# schematic.net
KiCad netlist of a schematic drawn in EAGLE
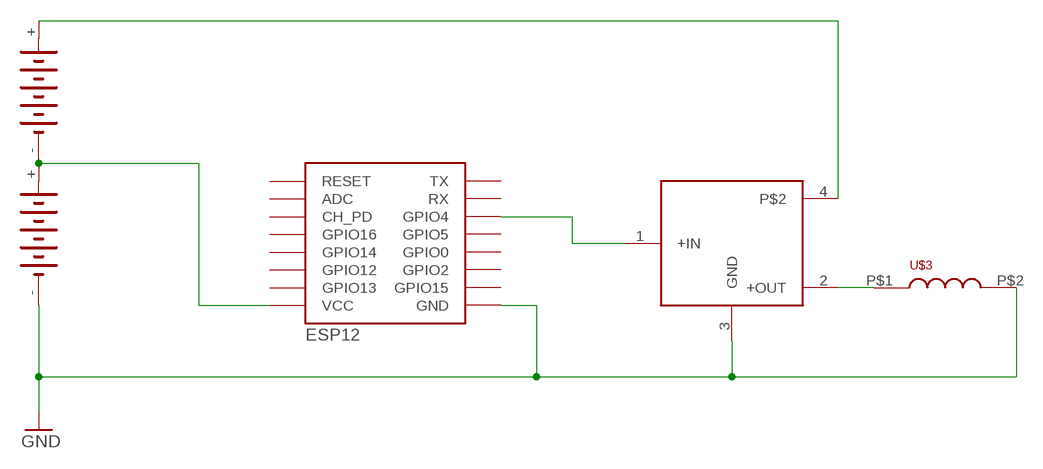
[diagram p0: schematic, sheet 1]

(export (version "E")
  (design (tool "Eeschema 10.0.6"))
  (components
    (comp (ref "G1")
      (value "NC1M")
      (footprint "eagle-import:NC1M")
      (libsource (lib "eagle-import") (part "NC1M"))
    )
    (comp (ref "G2")
      (value "NC1M")
      (footprint "eagle-import:NC1M")
      (libsource (lib "eagle-import") (part "NC1M"))
    )
    (comp (ref "U$1")
      (value "ESP12")
      (footprint "eagle-import:ESP12")
      (libsource (lib "eagle-import") (part "ESP12"))
    )
    (comp (ref "U$2")
      (value "H-BRIDGE")
      (footprint "eagle-import:H-BRIDGE")
      (libsource (lib "eagle-import") (part "H-BRIDGE"))
    )
    (comp (ref "U$3")
      (value "INDUCTOR")
      (footprint "eagle-import:SCD0403T-220M-N")
      (libsource (lib "eagle-import") (part "INDUCTOR"))
    )
  )
  (nets
    (net (code "1") (name "GND") (class "Default")
      (node (ref "G1") (pin "-") (pinfunction "-_-") (pintype "passive"))
      (node (ref "U$1") (pin "GND") (pinfunction "GND_GND") (pintype "bidirectional"))
      (node (ref "U$2") (pin "3") (pinfunction "GND_3") (pintype "bidirectional"))
      (node (ref "U$3") (pin "P$2") (pinfunction "2_P$2") (pintype "bidirectional"))
    )
    (net (code "2") (name "Net-(G1-Pad+)") (class "Default")
      (node (ref "G1") (pin "+") (pinfunction "+_+") (pintype "passive"))
      (node (ref "G2") (pin "-") (pinfunction "-_-") (pintype "passive"))
      (node (ref "U$1") (pin "VCC") (pinfunction "VCC_VCC") (pintype "bidirectional"))
    )
    (net (code "3") (name "Net-(U$2-+IN)") (class "Default")
      (node (ref "U$1") (pin "GPIO4") (pinfunction "GPIO4_GPIO4") (pintype "bidirectional"))
      (node (ref "U$2") (pin "1") (pinfunction "+IN_1") (pintype "bidirectional"))
    )
    (net (code "4") (name "Net-(U$2-+OUT)") (class "Default")
      (node (ref "U$2") (pin "2") (pinfunction "+OUT_2") (pintype "bidirectional"))
      (node (ref "U$3") (pin "P$1") (pinfunction "1_P$1") (pintype "bidirectional"))
    )
    (net (code "5") (name "Net-(U$2-P$2)") (class "Default")
      (node (ref "G2") (pin "+") (pinfunction "+_+") (pintype "passive"))
      (node (ref "U$2") (pin "4") (pinfunction "P$2_4") (pintype "bidirectional"))
    )
    (net (code "6") (name "unconnected-(G1-+-Pad+@1)") (class "Default")
      (node (ref "G1") (pin "+@1") (pinfunction "+_+@1") (pintype "passive"))
    )
    (net (code "7") (name "unconnected-(G2-+-Pad+@1)") (class "Default")
      (node (ref "G2") (pin "+@1") (pinfunction "+_+@1") (pintype "passive"))
    )
    (net (code "8") (name "unconnected-(U$1-PadADC)") (class "Default")
      (node (ref "U$1") (pin "ADC") (pinfunction "ADC_ADC") (pintype "bidirectional"))
    )
    (net (code "9") (name "unconnected-(U$1-PadCH_PD)") (class "Default")
      (node (ref "U$1") (pin "CH_PD") (pinfunction "CH_PD_CH_PD") (pintype "bidirectional"))
    )
    (net (code "10") (name "unconnected-(U$1-PadGPIO0)") (class "Default")
      (node (ref "U$1") (pin "GPIO0") (pinfunction "GPIO0_GPIO0") (pintype "bidirectional"))
    )
    (net (code "11") (name "unconnected-(U$1-PadGPIO2)") (class "Default")
      (node (ref "U$1") (pin "GPIO2") (pinfunction "GPIO2_GPIO2") (pintype "bidirectional"))
    )
    (net (code "12") (name "unconnected-(U$1-PadGPIO5)") (class "Default")
      (node (ref "U$1") (pin "GPIO5") (pinfunction "GPIO5_GPIO5") (pintype "bidirectional"))
    )
    (net (code "13") (name "unconnected-(U$1-PadGPIO12)") (class "Default")
      (node (ref "U$1") (pin "GPIO12") (pinfunction "GPIO12_GPIO12") (pintype "bidirectional"))
    )
    (net (code "14") (name "unconnected-(U$1-PadGPIO13)") (class "Default")
      (node (ref "U$1") (pin "GPIO13") (pinfunction "GPIO13_GPIO13") (pintype "bidirectional"))
    )
    (net (code "15") (name "unconnected-(U$1-PadGPIO14)") (class "Default")
      (node (ref "U$1") (pin "GPIO14") (pinfunction "GPIO14_GPIO14") (pintype "bidirectional"))
    )
    (net (code "16") (name "unconnected-(U$1-PadGPIO15)") (class "Default")
      (node (ref "U$1") (pin "GPIO15") (pinfunction "GPIO15_GPIO15") (pintype "bidirectional"))
    )
    (net (code "17") (name "unconnected-(U$1-PadGPIO16)") (class "Default")
      (node (ref "U$1") (pin "GPIO16") (pinfunction "GPIO16_GPIO16") (pintype "bidirectional"))
    )
    (net (code "18") (name "unconnected-(U$1-PadRESET)") (class "Default")
      (node (ref "U$1") (pin "RESET") (pinfunction "RESET_RESET") (pintype "bidirectional"))
    )
    (net (code "19") (name "unconnected-(U$1-PadRX)") (class "Default")
      (node (ref "U$1") (pin "RX") (pinfunction "RX_RX") (pintype "bidirectional"))
    )
    (net (code "20") (name "unconnected-(U$1-PadTX)") (class "Default")
      (node (ref "U$1") (pin "TX") (pinfunction "TX_TX") (pintype "bidirectional"))
    )
  )
)
